# PowerSupply.net
KiCad netlist of a schematic drawn in Altium Designer
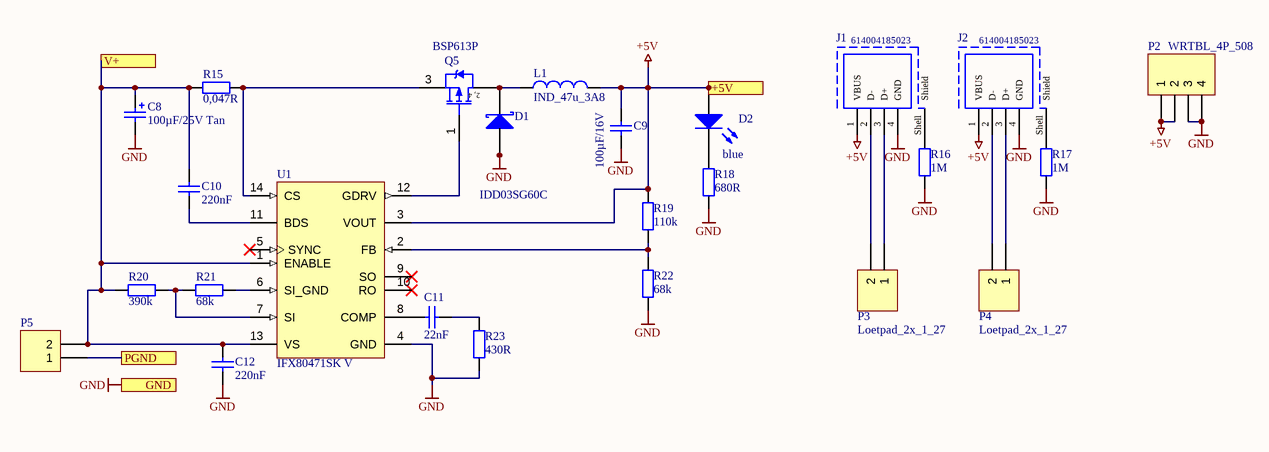
[diagram p0: PowerSupply.SchDoc]

(export (version "E")
  (design (tool "Eeschema 10.0.6"))
  (components
    (comp (ref "C8")
      (value "100µF/25V Tan")
      (footprint "C")
      (fields (field (name "VOLTAGE") "25v"))
      (libsource (lib "MCI_ALTIUM_LIB") (part "Cap_pol"))
    )
    (comp (ref "C9")
      (value "100µF/16V")
      (footprint "_1210")
      (fields (field (name "VOLTAGE") "?V"))
      (libsource (lib "MCI_ALTIUM_LIB") (part "Cap_nopol"))
    )
    (comp (ref "C10")
      (value "220nF")
      (footprint "_0805")
      (fields (field (name "VOLTAGE") "?V"))
      (libsource (lib "MCI_ALTIUM_LIB") (part "Cap_nopol"))
    )
    (comp (ref "C11")
      (value "22nF")
      (footprint "_0603")
      (libsource (lib "MCI_ALTIUM_LIB") (part "Cap_nopol"))
    )
    (comp (ref "C12")
      (value "220nF")
      (footprint "_0805")
      (fields (field (name "VOLTAGE") "?V"))
      (libsource (lib "MCI_ALTIUM_LIB") (part "Cap_nopol"))
    )
    (comp (ref "D1")
      (value "IDD03SG60C")
      (footprint "TO_252")
      (libsource (lib "MCI_ALTIUM_LIB") (part "30WQ06FN"))
    )
    (comp (ref "D2") (value "blue") (footprint "LED_0603") (libsource (lib "MCI_ALTIUM_LIB") (part "LED")))
    (comp (ref "J1")
      (value "614004185023")
      (footprint "614004185023")
      (description "USB 2.0 Type A Receptacle WR-COM, Vertical, THT, Short Type")
      (fields (field (name "PUBLISHER") "Wurth Elektronik"))
      (libsource (lib "ALTIUM-WR-COM_USB_20-rev19a") (part "614004185023"))
    )
    (comp (ref "J2")
      (value "614004185023")
      (footprint "614004185023")
      (description "USB 2.0 Type A Receptacle WR-COM, Vertical, THT, Short Type")
      (fields (field (name "PUBLISHER") "Wurth Elektronik"))
      (libsource (lib "ALTIUM-WR-COM_USB_20-rev19a") (part "614004185023"))
    )
    (comp (ref "L1")
      (value "IND_47u_3A8")
      (footprint "WE_PD_XXL")
      (description "Inductor")
      (libsource (lib "MCI_ALTIUM_LIB") (part "Inductor"))
    )
    (comp (ref "P2")
      (value "WRTBL_4P_508")
      (footprint "WRTBL_4P_508")
      (libsource (lib "MCI_ALTIUM_LIB") (part "Header 4"))
    )
    (comp (ref "P3")
      (value "Loetpad_2x_1_27")
      (footprint "Loetpad_2x_1_27")
      (libsource (lib "MCI_ALTIUM_LIB") (part "Header 2"))
    )
    (comp (ref "P4")
      (value "Loetpad_2x_1_27")
      (footprint "Loetpad_2x_1_27")
      (libsource (lib "MCI_ALTIUM_LIB") (part "Header 2"))
    )
    (comp (ref "P5")
      (value "WRTBL_2P_508")
      (footprint "WRTBL_2P_508")
      (libsource (lib "") (part "Header 2_1"))
    )
    (comp (ref "Q5")
      (value "BSP613P")
      (footprint "INF-PG-SOT223_SC-73_N")
      (fields (field (name "MANUFACTURER") "Infineon"))
      (libsource (lib "MCI_ALTIUM_LIB") (part "BSP613P"))
    )
    (comp (ref "R15") (value "0,047R") (footprint "_1206") (libsource (lib "") (part "Res_normal_1")))
    (comp (ref "R16") (value "1M") (footprint "_0603") (libsource (lib "MCI_ALTIUM_LIB") (part "Res_normal")))
    (comp (ref "R17") (value "1M") (footprint "_0603") (libsource (lib "MCI_ALTIUM_LIB") (part "Res_normal")))
    (comp (ref "R18")
      (value "680R")
      (footprint "_0603")
      (libsource (lib "MCI_ALTIUM_LIB") (part "Res_normal"))
    )
    (comp (ref "R19")
      (value "110k")
      (footprint "_0603")
      (libsource (lib "MCI_ALTIUM_LIB") (part "Res_normal"))
    )
    (comp (ref "R20") (value "390k") (footprint "_0603") (libsource (lib "") (part "Res_normal_1")))
    (comp (ref "R21") (value "68k") (footprint "_0603") (libsource (lib "") (part "Res_normal_1")))
    (comp (ref "R22")
      (value "68k")
      (footprint "_0603")
      (libsource (lib "MCI_ALTIUM_LIB") (part "Res_normal"))
    )
    (comp (ref "R23") (value "430R") (footprint "_0603") (libsource (lib "") (part "Res_normal_2")))
    (comp (ref "U1")
      (value "IFX80471SK V")
      (footprint "INF-PG-DSO-14-1_N")
      (description "Step-Down DC/DC Controller, 2,300 mA Iq, -40 to 125 degC, PG-DSO-14-1, Reel, Green")
      (fields (field (name "TOLERANCE") "3(5)%") (field (name "MANUFACTURER") "Infineon"))
      (libsource (lib "IFX80471SK V") (part "IFX80471SK V"))
    )
  )
  (nets
    (net (code "1") (name "+5V") (class "Default")
      (node (ref "C9") (pin "2") (pinfunction "2_2") (pintype "passive"))
      (node (ref "D2") (pin "1") (pinfunction "1_1") (pintype "passive"))
      (node (ref "J1") (pin "1") (pinfunction "VBUS_1") (pintype "passive"))
      (node (ref "J2") (pin "1") (pinfunction "VBUS_1") (pintype "passive"))
      (node (ref "L1") (pin "2") (pinfunction "2_2") (pintype "passive"))
      (node (ref "P2") (pin "1") (pinfunction "1_1") (pintype "passive"))
      (node (ref "P2") (pin "2") (pinfunction "2_2") (pintype "passive"))
      (node (ref "R19") (pin "2") (pinfunction "2_2") (pintype "passive"))
      (node (ref "U1") (pin "3") (pinfunction "VOUT_3") (pintype "power_in"))
    )
    (net (code "2") (name "/PGND") (class "Default")
      (node (ref "P5") (pin "1") (pinfunction "1_1") (pintype "passive"))
    )
    (net (code "3") (name "/V+") (class "Default")
      (node (ref "C10") (pin "2") (pinfunction "2_2") (pintype "passive"))
      (node (ref "C12") (pin "2") (pinfunction "2_2") (pintype "passive"))
      (node (ref "C8") (pin "1") (pinfunction "1_1") (pintype "passive"))
      (node (ref "P5") (pin "2") (pinfunction "2_2") (pintype "passive"))
      (node (ref "R15") (pin "1") (pinfunction "1_1") (pintype "passive"))
      (node (ref "R20") (pin "1") (pinfunction "1_1") (pintype "passive"))
      (node (ref "U1") (pin "1") (pinfunction "ENABLE_1") (pintype "input"))
      (node (ref "U1") (pin "13") (pinfunction "VS_13") (pintype "power_in"))
    )
    (net (code "4") (name "GND") (class "Default")
      (node (ref "C12") (pin "1") (pinfunction "1_1") (pintype "passive"))
      (node (ref "C8") (pin "2") (pinfunction "2_2") (pintype "passive"))
      (node (ref "C9") (pin "1") (pinfunction "1_1") (pintype "passive"))
      (node (ref "D1") (pin "1") (pinfunction "1_1") (pintype "passive"))
      (node (ref "D1") (pin "2") (pinfunction "2_2") (pintype "passive"))
      (node (ref "J1") (pin "4") (pinfunction "GND_4") (pintype "passive"))
      (node (ref "J2") (pin "4") (pinfunction "GND_4") (pintype "passive"))
      (node (ref "P2") (pin "3") (pinfunction "3_3") (pintype "passive"))
      (node (ref "P2") (pin "4") (pinfunction "4_4") (pintype "passive"))
      (node (ref "R16") (pin "1") (pinfunction "1_1") (pintype "passive"))
      (node (ref "R17") (pin "1") (pinfunction "1_1") (pintype "passive"))
      (node (ref "R18") (pin "1") (pinfunction "1_1") (pintype "passive"))
      (node (ref "R22") (pin "1") (pinfunction "1_1") (pintype "passive"))
      (node (ref "R23") (pin "2") (pinfunction "2_2") (pintype "passive"))
      (node (ref "U1") (pin "4") (pinfunction "GND_4") (pintype "power_in"))
    )
    (net (code "5") (name "Net-(C11-Pad2)") (class "Default")
      (node (ref "C11") (pin "2") (pinfunction "2_2") (pintype "passive"))
      (node (ref "R23") (pin "1") (pinfunction "1_1") (pintype "passive"))
    )
    (net (code "6") (name "Net-(D1-Pad3)") (class "Default")
      (node (ref "D1") (pin "3") (pinfunction "3_3") (pintype "passive"))
      (node (ref "L1") (pin "1") (pinfunction "1_1") (pintype "passive"))
      (node (ref "Q5") (pin "2") (pinfunction "DRAIN_2") (pintype "passive"))
      (node (ref "Q5") (pin "4") (pinfunction "DRAIN_4") (pintype "passive"))
    )
    (net (code "7") (name "Net-(D2-Pad2)") (class "Default")
      (node (ref "D2") (pin "2") (pinfunction "2_2") (pintype "passive"))
      (node (ref "R18") (pin "2") (pinfunction "2_2") (pintype "passive"))
    )
    (net (code "8") (name "Net-(J1-D+)") (class "Default")
      (node (ref "J1") (pin "3") (pinfunction "D+_3") (pintype "passive"))
      (node (ref "P3") (pin "1") (pinfunction "1_1") (pintype "passive"))
    )
    (net (code "9") (name "Net-(J1-D-)") (class "Default")
      (node (ref "J1") (pin "2") (pinfunction "D-_2") (pintype "passive"))
      (node (ref "P3") (pin "2") (pinfunction "2_2") (pintype "passive"))
    )
    (net (code "10") (name "Net-(J1-Shield)") (class "Default")
      (node (ref "J1") (pin "Shell") (pinfunction "Shield_Shell") (pintype "passive"))
      (node (ref "R16") (pin "2") (pinfunction "2_2") (pintype "passive"))
    )
    (net (code "11") (name "Net-(J2-D+)") (class "Default")
      (node (ref "J2") (pin "3") (pinfunction "D+_3") (pintype "passive"))
      (node (ref "P4") (pin "1") (pinfunction "1_1") (pintype "passive"))
    )
    (net (code "12") (name "Net-(J2-D-)") (class "Default")
      (node (ref "J2") (pin "2") (pinfunction "D-_2") (pintype "passive"))
      (node (ref "P4") (pin "2") (pinfunction "2_2") (pintype "passive"))
    )
    (net (code "13") (name "Net-(J2-Shield)") (class "Default")
      (node (ref "J2") (pin "Shell") (pinfunction "Shield_Shell") (pintype "passive"))
      (node (ref "R17") (pin "2") (pinfunction "2_2") (pintype "passive"))
    )
    (net (code "14") (name "Net-(Q5-GATE)") (class "Default")
      (node (ref "Q5") (pin "1") (pinfunction "GATE_1") (pintype "passive"))
      (node (ref "U1") (pin "12") (pinfunction "GDRV_12") (pintype "output"))
    )
    (net (code "15") (name "Net-(Q5-SOURCE)") (class "Default")
      (node (ref "Q5") (pin "3") (pinfunction "SOURCE_3") (pintype "passive"))
      (node (ref "R15") (pin "2") (pinfunction "2_2") (pintype "passive"))
      (node (ref "U1") (pin "14") (pinfunction "CS_14") (pintype "input"))
    )
    (net (code "16") (name "Net-(U1-BDS)") (class "Default")
      (node (ref "C10") (pin "1") (pinfunction "1_1") (pintype "passive"))
      (node (ref "U1") (pin "11") (pinfunction "BDS_11") (pintype "power_in"))
    )
    (net (code "17") (name "Net-(U1-COMP)") (class "Default")
      (node (ref "C11") (pin "1") (pinfunction "1_1") (pintype "passive"))
      (node (ref "U1") (pin "8") (pinfunction "COMP_8") (pintype "passive"))
    )
    (net (code "18") (name "Net-(U1-FB)") (class "Default")
      (node (ref "R19") (pin "1") (pinfunction "1_1") (pintype "passive"))
      (node (ref "R22") (pin "2") (pinfunction "2_2") (pintype "passive"))
      (node (ref "U1") (pin "2") (pinfunction "FB_2") (pintype "input"))
    )
    (net (code "19") (name "Net-(U1-SI)") (class "Default")
      (node (ref "R20") (pin "2") (pinfunction "2_2") (pintype "passive"))
      (node (ref "R21") (pin "1") (pinfunction "1_1") (pintype "passive"))
      (node (ref "U1") (pin "7") (pinfunction "SI_7") (pintype "input"))
    )
    (net (code "20") (name "Net-(U1-SI_GND)") (class "Default")
      (node (ref "R21") (pin "2") (pinfunction "2_2") (pintype "passive"))
      (node (ref "U1") (pin "6") (pinfunction "SI_GND_6") (pintype "input"))
    )
    (net (code "21") (name "unconnected-(U1-RO-Pad10)") (class "Default")
      (node (ref "U1") (pin "10") (pinfunction "RO_10") (pintype "open_collector+no_connect"))
    )
    (net (code "22") (name "unconnected-(U1-SO-Pad9)") (class "Default")
      (node (ref "U1") (pin "9") (pinfunction "SO_9") (pintype "open_collector+no_connect"))
    )
    (net (code "23") (name "unconnected-(U1-SYNC-Pad5)") (class "Default")
      (node (ref "U1") (pin "5") (pinfunction "SYNC_5") (pintype "input+no_connect"))
    )
  )
)
